# NA-board.net
KiCad netlist of a schematic drawn in EAGLE
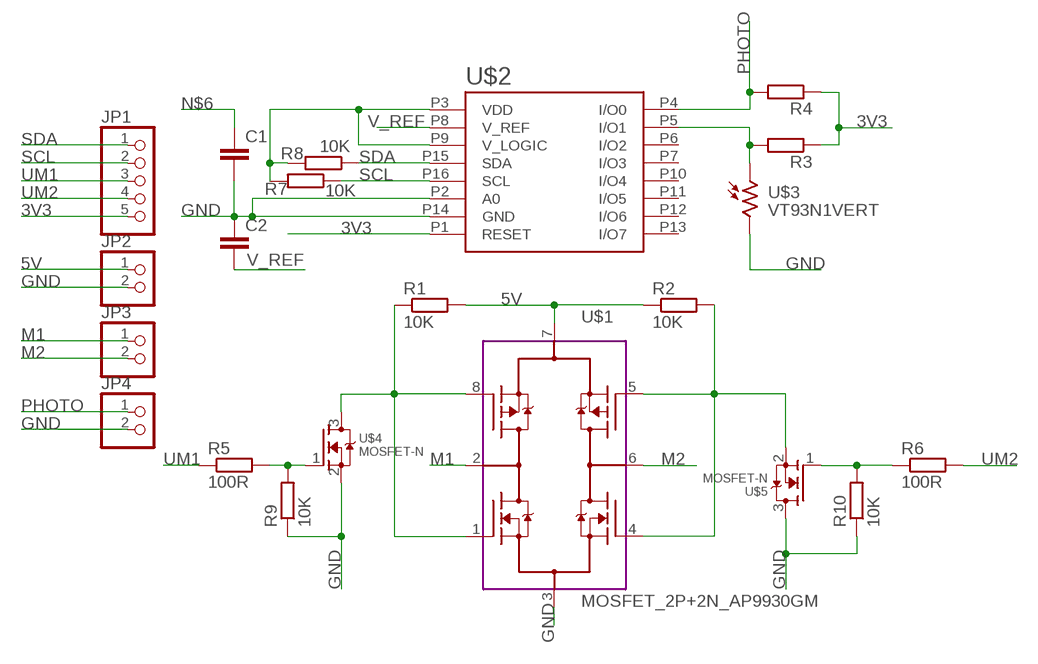
[diagram p0: schematic, sheet 1]

(export (version "E")
  (design (tool "Eeschema 10.0.6"))
  (components
    (comp (ref "C1")
      (value "C-EUC0603")
      (footprint "eagle-import:C0603")
      (libsource (lib "eagle-import") (part "C-EUC0603"))
    )
    (comp (ref "C2")
      (value "C-EUC0603")
      (footprint "eagle-import:C0603")
      (libsource (lib "eagle-import") (part "C-EUC0603"))
    )
    (comp (ref "JP1")
      (value "PINHD-1X5")
      (footprint "eagle-import:1X05")
      (libsource (lib "eagle-import") (part "PINHD-1X5"))
    )
    (comp (ref "JP2")
      (value "PINHD-1X2")
      (footprint "eagle-import:1X02")
      (libsource (lib "eagle-import") (part "PINHD-1X2"))
    )
    (comp (ref "JP3")
      (value "PINHD-1X2")
      (footprint "eagle-import:1X02")
      (libsource (lib "eagle-import") (part "PINHD-1X2"))
    )
    (comp (ref "JP4")
      (value "PINHD-1X2")
      (footprint "eagle-import:1X02")
      (libsource (lib "eagle-import") (part "PINHD-1X2"))
    )
    (comp (ref "R1")
      (value "10K")
      (footprint "eagle-import:R0603")
      (libsource (lib "eagle-import") (part "R-EU_R0603"))
    )
    (comp (ref "R2")
      (value "10K")
      (footprint "eagle-import:R0603")
      (libsource (lib "eagle-import") (part "R-EU_R0603"))
    )
    (comp (ref "R3")
      (value "R-EU_R0603")
      (footprint "eagle-import:R0603")
      (libsource (lib "eagle-import") (part "R-EU_R0603"))
    )
    (comp (ref "R4")
      (value "R-EU_R0603")
      (footprint "eagle-import:R0603")
      (libsource (lib "eagle-import") (part "R-EU_R0603"))
    )
    (comp (ref "R5")
      (value "100R")
      (footprint "eagle-import:R0603")
      (libsource (lib "eagle-import") (part "R-EU_R0603"))
    )
    (comp (ref "R6")
      (value "100R")
      (footprint "eagle-import:R0603")
      (libsource (lib "eagle-import") (part "R-EU_R0603"))
    )
    (comp (ref "R7")
      (value "10K")
      (footprint "eagle-import:R0603")
      (libsource (lib "eagle-import") (part "R-EU_R0603"))
    )
    (comp (ref "R8")
      (value "10K")
      (footprint "eagle-import:R0603")
      (libsource (lib "eagle-import") (part "R-EU_R0603"))
    )
    (comp (ref "R9")
      (value "10K")
      (footprint "eagle-import:R0603")
      (libsource (lib "eagle-import") (part "R-EU_R0603"))
    )
    (comp (ref "R10")
      (value "10K")
      (footprint "eagle-import:R0603")
      (libsource (lib "eagle-import") (part "R-EU_R0603"))
    )
    (comp (ref "U$1")
      (value "MOSFET_2P+2N_AP9930GM")
      (footprint "eagle-import:SO8")
      (libsource (lib "eagle-import") (part "MOSFET_2P+2N_AP9930GM"))
    )
    (comp (ref "U$2")
      (value "AD5593R")
      (footprint "eagle-import:AD5593R")
      (libsource (lib "eagle-import") (part "AD5593R"))
    )
    (comp (ref "U$3")
      (value "VT93N1VERT")
      (footprint "eagle-import:VT93N1-VERT")
      (libsource (lib "eagle-import") (part "VT93N1VERT"))
    )
    (comp (ref "U$4")
      (value "MOSFET-N")
      (footprint "eagle-import:SOT23-3")
      (libsource (lib "eagle-import") (part "MOSFET-N"))
    )
    (comp (ref "U$5")
      (value "MOSFET-N")
      (footprint "eagle-import:SOT23-3")
      (libsource (lib "eagle-import") (part "MOSFET-N"))
    )
  )
  (nets
    (net (code "1") (name "/3V3") (class "Default")
      (node (ref "JP1") (pin "5") (pinfunction "5_5") (pintype "passive"))
      (node (ref "R3") (pin "1") (pinfunction "1_1") (pintype "passive"))
      (node (ref "R4") (pin "1") (pinfunction "1_1") (pintype "passive"))
      (node (ref "R7") (pin "2") (pinfunction "2_2") (pintype "passive"))
      (node (ref "R8") (pin "2") (pinfunction "2_2") (pintype "passive"))
      (node (ref "U$2") (pin "P1") (pinfunction "RESET_P1") (pintype "bidirectional"))
      (node (ref "U$2") (pin "P3") (pinfunction "VDD_P3") (pintype "bidirectional"))
      (node (ref "U$2") (pin "P9") (pinfunction "V_LOGIC_P9") (pintype "bidirectional"))
    )
    (net (code "2") (name "/5V") (class "Default")
      (node (ref "JP2") (pin "1") (pinfunction "1_1") (pintype "passive"))
      (node (ref "R1") (pin "2") (pinfunction "2_2") (pintype "passive"))
      (node (ref "R2") (pin "1") (pinfunction "1_1") (pintype "passive"))
      (node (ref "U$1") (pin "7") (pinfunction "P1P2S_7") (pintype "passive"))
    )
    (net (code "3") (name "/GND") (class "Default")
      (node (ref "C1") (pin "2") (pinfunction "2_2") (pintype "passive"))
      (node (ref "C2") (pin "1") (pinfunction "1_1") (pintype "passive"))
      (node (ref "JP2") (pin "2") (pinfunction "2_2") (pintype "passive"))
      (node (ref "JP4") (pin "2") (pinfunction "2_2") (pintype "passive"))
      (node (ref "R10") (pin "1") (pinfunction "1_1") (pintype "passive"))
      (node (ref "R9") (pin "1") (pinfunction "1_1") (pintype "passive"))
      (node (ref "U$1") (pin "3") (pinfunction "N1N2S_3") (pintype "passive"))
      (node (ref "U$2") (pin "P14") (pinfunction "GND_P14") (pintype "bidirectional"))
      (node (ref "U$2") (pin "P2") (pinfunction "A0_P2") (pintype "bidirectional"))
      (node (ref "U$3") (pin "P$2") (pinfunction "2_P$2") (pintype "passive"))
      (node (ref "U$4") (pin "2") (pinfunction "S_2") (pintype "bidirectional"))
      (node (ref "U$5") (pin "3") (pinfunction "D_3") (pintype "bidirectional"))
    )
    (net (code "4") (name "/M1") (class "Default")
      (node (ref "JP3") (pin "1") (pinfunction "1_1") (pintype "passive"))
      (node (ref "U$1") (pin "2") (pinfunction "P1N1D_2") (pintype "passive"))
    )
    (net (code "5") (name "/M2") (class "Default")
      (node (ref "JP3") (pin "2") (pinfunction "2_2") (pintype "passive"))
      (node (ref "U$1") (pin "6") (pinfunction "P2N2D_6") (pintype "passive"))
    )
    (net (code "6") (name "/N$6") (class "Default")
      (node (ref "C1") (pin "1") (pinfunction "1_1") (pintype "passive"))
    )
    (net (code "7") (name "/PHOTO") (class "Default")
      (node (ref "JP4") (pin "1") (pinfunction "1_1") (pintype "passive"))
      (node (ref "R4") (pin "2") (pinfunction "2_2") (pintype "passive"))
      (node (ref "U$2") (pin "P4") (pinfunction "I/O0_P4") (pintype "bidirectional"))
    )
    (net (code "8") (name "/SCL") (class "Default")
      (node (ref "JP1") (pin "2") (pinfunction "2_2") (pintype "passive"))
      (node (ref "R7") (pin "1") (pinfunction "1_1") (pintype "passive"))
      (node (ref "U$2") (pin "P16") (pinfunction "SCL_P16") (pintype "bidirectional"))
    )
    (net (code "9") (name "/SDA") (class "Default")
      (node (ref "JP1") (pin "1") (pinfunction "1_1") (pintype "passive"))
      (node (ref "R8") (pin "1") (pinfunction "1_1") (pintype "passive"))
      (node (ref "U$2") (pin "P15") (pinfunction "SDA_P15") (pintype "bidirectional"))
    )
    (net (code "10") (name "/UM1") (class "Default")
      (node (ref "JP1") (pin "3") (pinfunction "3_3") (pintype "passive"))
      (node (ref "R5") (pin "1") (pinfunction "1_1") (pintype "passive"))
    )
    (net (code "11") (name "/UM2") (class "Default")
      (node (ref "JP1") (pin "4") (pinfunction "4_4") (pintype "passive"))
      (node (ref "R6") (pin "2") (pinfunction "2_2") (pintype "passive"))
    )
    (net (code "12") (name "/V_REF") (class "Default")
      (node (ref "C2") (pin "2") (pinfunction "2_2") (pintype "passive"))
      (node (ref "U$2") (pin "P8") (pinfunction "V_REF_P8") (pintype "bidirectional"))
    )
    (net (code "13") (name "Net-(U$1-N1G)") (class "Default")
      (node (ref "R1") (pin "1") (pinfunction "1_1") (pintype "passive"))
      (node (ref "U$1") (pin "1") (pinfunction "N1G_1") (pintype "passive"))
      (node (ref "U$1") (pin "8") (pinfunction "P1G_8") (pintype "passive"))
      (node (ref "U$4") (pin "3") (pinfunction "D_3") (pintype "bidirectional"))
    )
    (net (code "14") (name "Net-(U$1-N2G)") (class "Default")
      (node (ref "R2") (pin "2") (pinfunction "2_2") (pintype "passive"))
      (node (ref "U$1") (pin "4") (pinfunction "N2G_4") (pintype "passive"))
      (node (ref "U$1") (pin "5") (pinfunction "P2G_5") (pintype "passive"))
      (node (ref "U$5") (pin "2") (pinfunction "S_2") (pintype "bidirectional"))
    )
    (net (code "15") (name "Net-(U$2-I{slash}O1)") (class "Default")
      (node (ref "R3") (pin "2") (pinfunction "2_2") (pintype "passive"))
      (node (ref "U$2") (pin "P5") (pinfunction "I/O1_P5") (pintype "bidirectional"))
      (node (ref "U$3") (pin "P$1") (pinfunction "1_P$1") (pintype "passive"))
    )
    (net (code "16") (name "Net-(U$4-G)") (class "Default")
      (node (ref "R5") (pin "2") (pinfunction "2_2") (pintype "passive"))
      (node (ref "R9") (pin "2") (pinfunction "2_2") (pintype "passive"))
      (node (ref "U$4") (pin "1") (pinfunction "G_1") (pintype "bidirectional"))
    )
    (net (code "17") (name "Net-(U$5-G)") (class "Default")
      (node (ref "R10") (pin "2") (pinfunction "2_2") (pintype "passive"))
      (node (ref "R6") (pin "1") (pinfunction "1_1") (pintype "passive"))
      (node (ref "U$5") (pin "1") (pinfunction "G_1") (pintype "bidirectional"))
    )
    (net (code "18") (name "unconnected-(U$2-I{slash}O2-PadP6)") (class "Default")
      (node (ref "U$2") (pin "P6") (pinfunction "I/O2_P6") (pintype "bidirectional"))
    )
    (net (code "19") (name "unconnected-(U$2-I{slash}O3-PadP7)") (class "Default")
      (node (ref "U$2") (pin "P7") (pinfunction "I/O3_P7") (pintype "bidirectional"))
    )
    (net (code "20") (name "unconnected-(U$2-I{slash}O4-PadP10)") (class "Default")
      (node (ref "U$2") (pin "P10") (pinfunction "I/O4_P10") (pintype "bidirectional"))
    )
    (net (code "21") (name "unconnected-(U$2-I{slash}O5-PadP11)") (class "Default")
      (node (ref "U$2") (pin "P11") (pinfunction "I/O5_P11") (pintype "bidirectional"))
    )
    (net (code "22") (name "unconnected-(U$2-I{slash}O6-PadP12)") (class "Default")
      (node (ref "U$2") (pin "P12") (pinfunction "I/O6_P12") (pintype "bidirectional"))
    )
    (net (code "23") (name "unconnected-(U$2-I{slash}O7-PadP13)") (class "Default")
      (node (ref "U$2") (pin "P13") (pinfunction "I/O7_P13") (pintype "bidirectional"))
    )
  )
)
